# rapidshark-dart-detector-mk-2_1.net
KiCad netlist of a schematic drawn in EAGLE
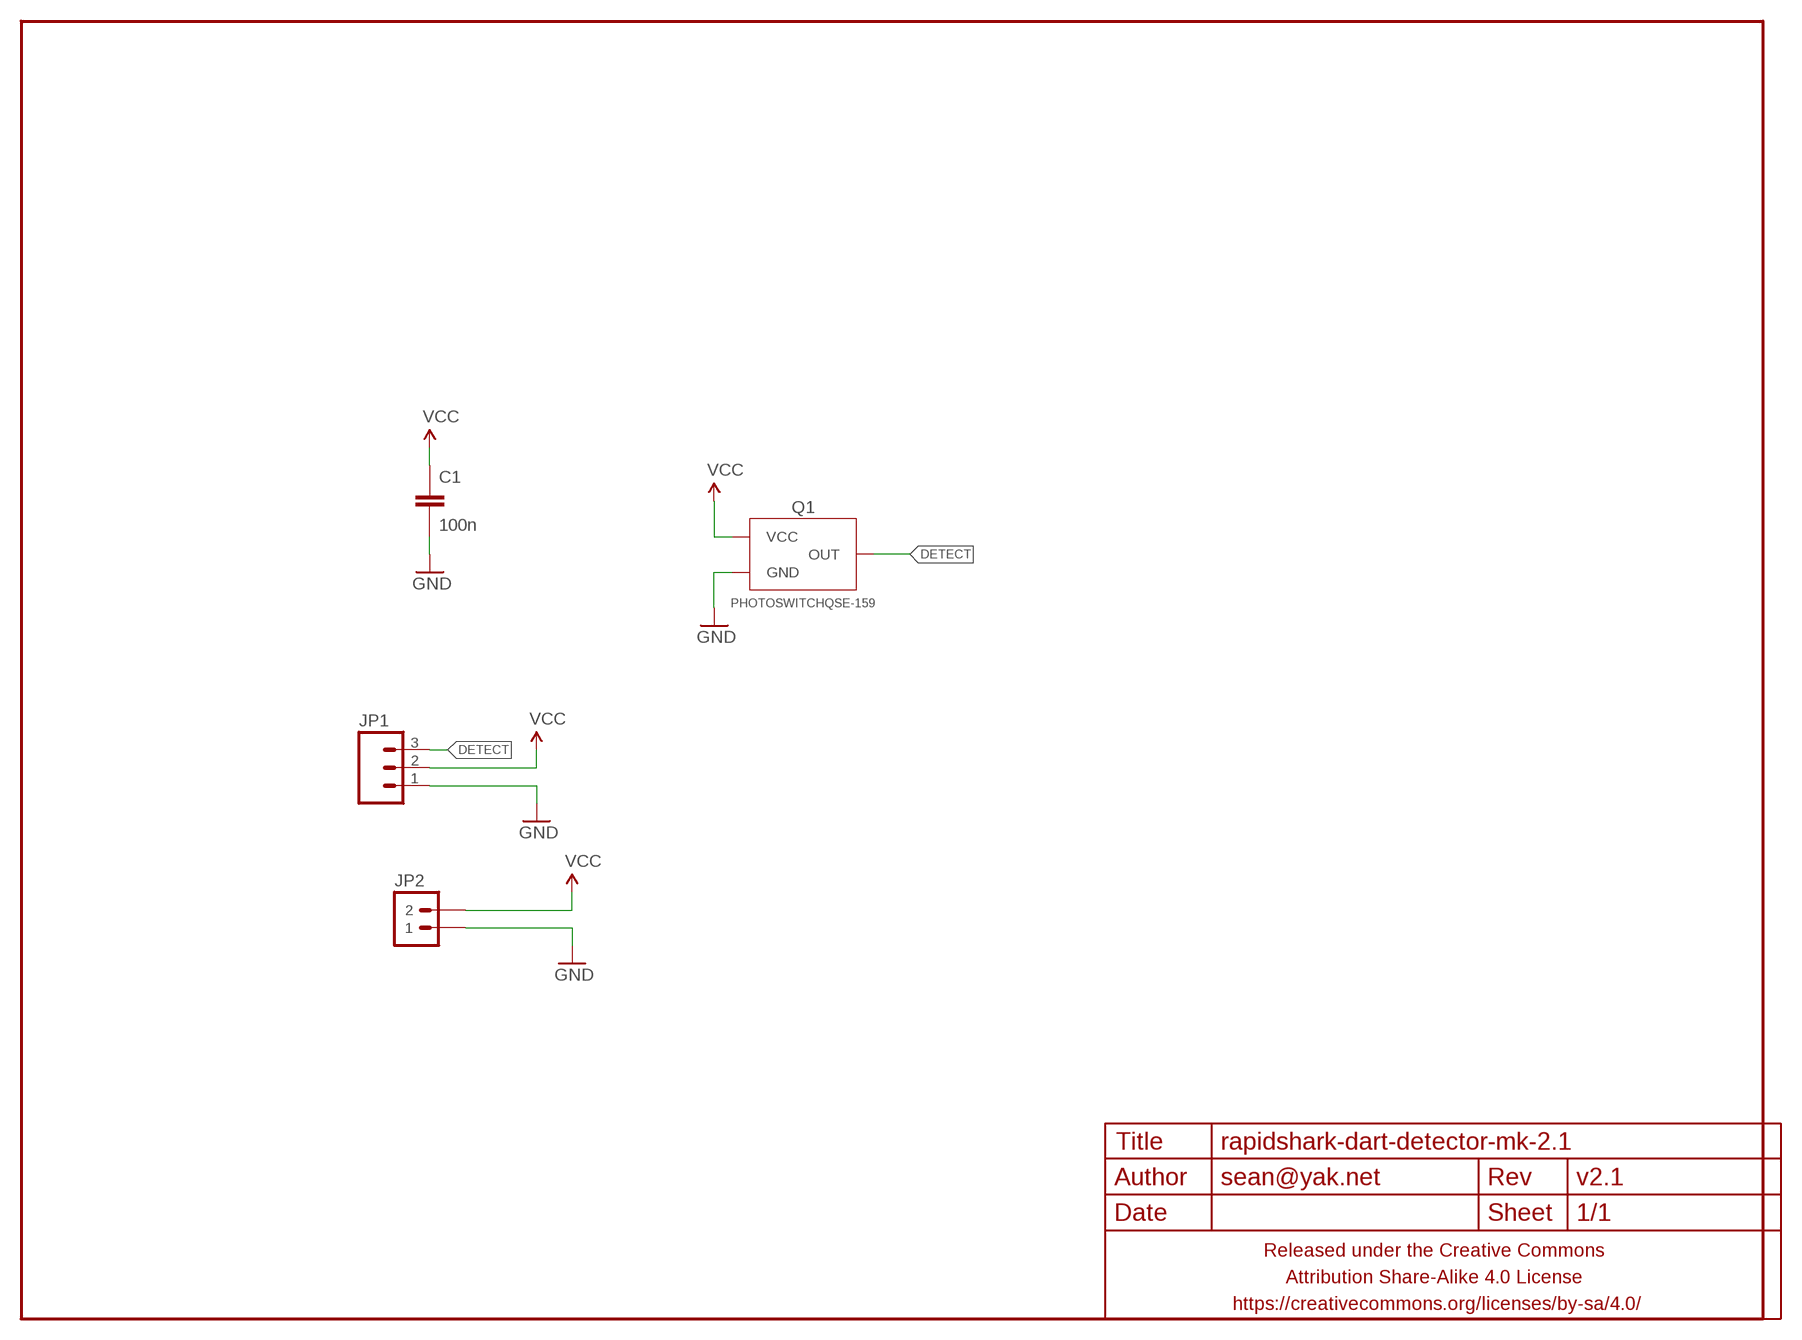
[diagram p0: schematic, sheet 1]

(export (version "E")
  (design (tool "Eeschema 10.0.6"))
  (components
    (comp (ref "C1")
      (value "100n")
      (footprint "eagle-import:C025-024X044")
      (libsource (lib "eagle-import") (part "CAPACITOR-CERAMIC025-024X044"))
    )
    (comp (ref "FRAME1")
      (value "FRAME-LETTERNO_PACKAGE")
      (footprint "eagle-import:DUMMY")
      (fields (field (name "DESIGNER") "sean@yak.net") (field (name "VERSION") "v2.1"))
      (libsource (lib "eagle-import") (part "FRAME-LETTERNO_PACKAGE"))
    )
    (comp (ref "JP1")
      (value "M03JST-PTH")
      (footprint "eagle-import:JST-3-PH-RA-PTH")
      (libsource (lib "eagle-import") (part "M03JST-PTH"))
    )
    (comp (ref "JP2")
      (value "M02JST-PTH-RA-R+")
      (footprint "eagle-import:JST-2-PH-RA-PTH-R+")
      (libsource (lib "eagle-import") (part "M02JST-PTH-RA-R+"))
    )
    (comp (ref "Q1")
      (value "PHOTOSWITCHQSE-159")
      (footprint "eagle-import:QSE-159")
      (libsource (lib "eagle-import") (part "PHOTOSWITCHQSE-159"))
    )
  )
  (nets
    (net (code "1") (name "DETECT") (class "Default")
      (node (ref "JP1") (pin "3") (pinfunction "3_3") (pintype "passive"))
      (node (ref "Q1") (pin "2") (pinfunction "OUT_2") (pintype "bidirectional"))
    )
    (net (code "2") (name "GND") (class "Default")
      (node (ref "C1") (pin "2") (pinfunction "2_2") (pintype "passive"))
      (node (ref "JP1") (pin "1") (pinfunction "1_1") (pintype "passive"))
      (node (ref "JP2") (pin "1") (pinfunction "1_1") (pintype "passive"))
      (node (ref "Q1") (pin "1") (pinfunction "GND_1") (pintype "bidirectional"))
    )
    (net (code "3") (name "VCC") (class "Default")
      (node (ref "C1") (pin "1") (pinfunction "1_1") (pintype "passive"))
      (node (ref "JP1") (pin "2") (pinfunction "2_2") (pintype "passive"))
      (node (ref "JP2") (pin "2") (pinfunction "2_2") (pintype "passive"))
      (node (ref "Q1") (pin "3") (pinfunction "VCC_3") (pintype "bidirectional"))
    )
  )
)
